# STM32_microcontroller_Power.net
KiCad netlist of a schematic drawn in Altium Designer
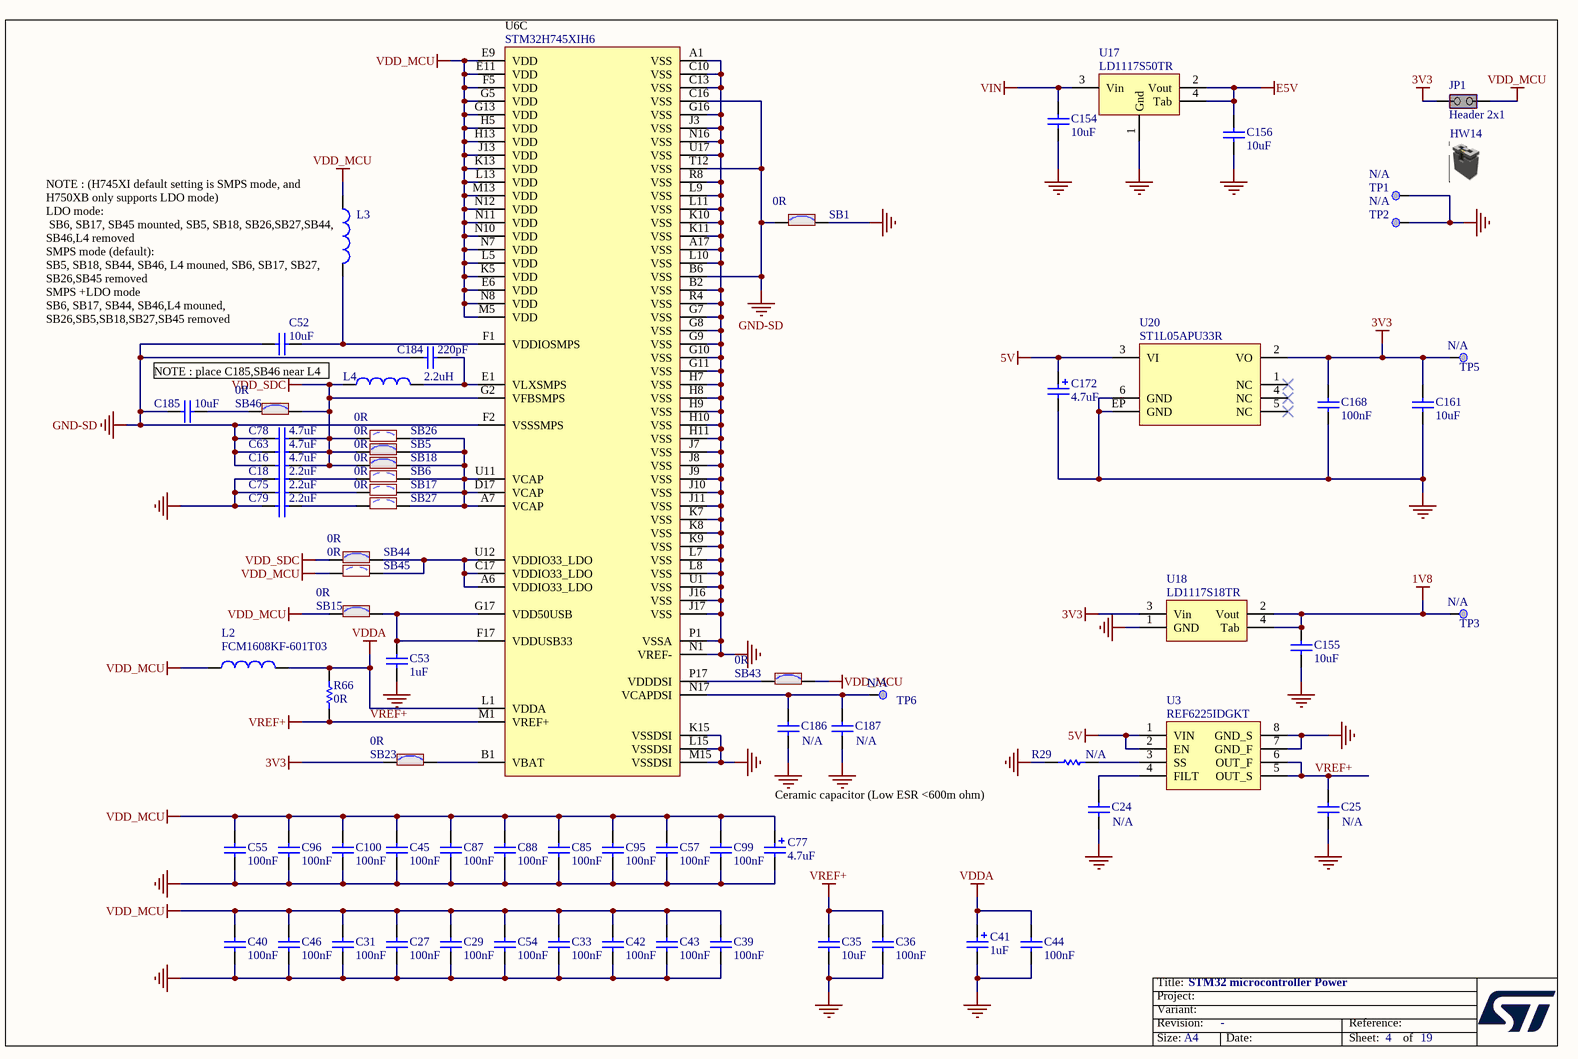
[diagram p0: STM32_microcontroller_Power.SchDoc]

(export (version "E")
  (design (tool "Eeschema 10.0.6"))
  (components
    (comp (ref "C16")
      (value "4.7uF")
      (footprint "C0402")
      (description "Capacitor, MLCC, 4.7uF, 6V3, X5R, 20%, 0402, T=0,5mm")
      (fields
        (field (name "INTERNAL_PART_NUMBER") "MCD-01356")
        (field (name "MANUFACTURER_PART_NUMBER") "GRM155R60J475ME47")
        (field (name "PROVIDED_BY") "Subcon")
      )
      (libsource (lib "MCD_PARTS_database") (part "Capacitor"))
    )
    (comp (ref "C18")
      (value "2.2uF")
      (footprint "C0603")
      (description "Capacitor, MLCC, 2.2uF, 10V, X5R, 10%, 0603, T=0,8mm")
      (fields
        (field (name "INTERNAL_PART_NUMBER") "MCD-00012")
        (field (name "MANUFACTURER_PART_NUMBER") "CC0603KRX5R6BB225")
        (field (name "PROVIDED_BY") "Subcon")
      )
      (libsource (lib "MCD_PARTS_database") (part "Capacitor"))
    )
    (comp (ref "C24")
      (value "N/A")
      (footprint "C0603")
      (description "Capacitor, MLCC, 1uF, 16V, X5R, 10%, 0603, T=0,8mm")
      (fields
        (field (name "INTERNAL_PART_NUMBER") "MCD-00010")
        (field (name "MANUFACTURER_PART_NUMBER") "CC0603KRX5R7BB105")
        (field (name "PROVIDED_BY") "Subcon")
      )
      (libsource (lib "MCD_PARTS_database") (part "Capacitor"))
    )
    (comp (ref "C25")
      (value "N/A")
      (footprint "C1210")
      (description "Capacitor, MLCC, 22uF, 16V, 1210, X7R, 20%, T=2,5mm, ESR 2mohm@410KHz")
      (fields
        (field (name "INTERNAL_PART_NUMBER") "MCD-00614")
        (field (name "MANUFACTURER_PART_NUMBER") "GCM32ER71C226ME19")
        (field (name "PROVIDED_BY") "Subcon")
      )
      (libsource (lib "MCD_PARTS_database") (part "Capacitor"))
    )
    (comp (ref "C27")
      (value "100nF")
      (footprint "C0402")
      (description "Capacitor, MLCC, 100nF, 16V, X7R, +/-10%, 0402, T=0.5mm")
      (fields
        (field (name "INTERNAL_PART_NUMBER") "MCD-00006")
        (field (name "MANUFACTURER_PART_NUMBER") "CC0402KRX7R7BB104")
      )
      (libsource (lib "MCD_PARTS_database") (part "Capacitor"))
    )
    (comp (ref "C29")
      (value "100nF")
      (footprint "C0402")
      (description "Capacitor, MLCC, 100nF, 16V, X7R, +/-10%, 0402, T=0.5mm")
      (fields
        (field (name "INTERNAL_PART_NUMBER") "MCD-00006")
        (field (name "MANUFACTURER_PART_NUMBER") "CC0402KRX7R7BB104")
      )
      (libsource (lib "MCD_PARTS_database") (part "Capacitor"))
    )
    (comp (ref "C31")
      (value "100nF")
      (footprint "C0402")
      (description "Capacitor, MLCC, 100nF, 16V, X7R, +/-10%, 0402, T=0.5mm")
      (fields
        (field (name "INTERNAL_PART_NUMBER") "MCD-00006")
        (field (name "MANUFACTURER_PART_NUMBER") "CC0402KRX7R7BB104")
      )
      (libsource (lib "MCD_PARTS_database") (part "Capacitor"))
    )
    (comp (ref "C33")
      (value "100nF")
      (footprint "C0402")
      (description "Capacitor, MLCC, 100nF, 16V, X7R, +/-10%, 0402, T=0.5mm")
      (fields
        (field (name "INTERNAL_PART_NUMBER") "MCD-00006")
        (field (name "MANUFACTURER_PART_NUMBER") "CC0402KRX7R7BB104")
      )
      (libsource (lib "MCD_PARTS_database") (part "Capacitor"))
    )
    (comp (ref "C35")
      (value "10uF")
      (footprint "C0805")
      (description "Capacitor, MLCC, 10uF, 25V, X5R, 10%, 0805, T=0,85mm")
      (fields
        (field (name "INTERNAL_PART_NUMBER") "MCD-00014")
        (field (name "MANUFACTURER_PART_NUMBER") "CC0805KRX5R8BB106")
        (field (name "PROVIDED_BY") "Subcon")
      )
      (libsource (lib "MCD_PARTS_database") (part "Capacitor"))
    )
    (comp (ref "C36")
      (value "100nF")
      (footprint "C0402")
      (description "Capacitor, MLCC, 100nF, 16V, X7R, +/-10%, 0402, T=0.5mm")
      (fields
        (field (name "INTERNAL_PART_NUMBER") "MCD-00006")
        (field (name "MANUFACTURER_PART_NUMBER") "CC0402KRX7R7BB104")
      )
      (libsource (lib "MCD_PARTS_database") (part "Capacitor"))
    )
    (comp (ref "C39")
      (value "100nF")
      (footprint "C0402")
      (description "Capacitor, MLCC, 100nF, 16V, X7R, +/-10%, 0402, T=0.5mm")
      (fields
        (field (name "INTERNAL_PART_NUMBER") "MCD-00006")
        (field (name "MANUFACTURER_PART_NUMBER") "CC0402KRX7R7BB104")
      )
      (libsource (lib "MCD_PARTS_database") (part "Capacitor"))
    )
    (comp (ref "C40")
      (value "100nF")
      (footprint "C0402")
      (description "Capacitor, MLCC, 100nF, 16V, X7R, +/-10%, 0402, T=0.5mm")
      (fields
        (field (name "INTERNAL_PART_NUMBER") "MCD-00006")
        (field (name "MANUFACTURER_PART_NUMBER") "CC0402KRX7R7BB104")
      )
      (libsource (lib "MCD_PARTS_database") (part "Capacitor"))
    )
    (comp (ref "C41")
      (value "1uF")
      (footprint "CPOL_VISHAY_TANTAL-595D_1407_H220")
      (description "Capacitor, Tantalum, 1uF, 35V, +/-10%, 595D case A")
      (fields
        (field (name "INTERNAL_PART_NUMBER") "MCD-00594")
        (field (name "MANUFACTURER_PART_NUMBER") "595D105X9035A2T")
        (field (name "PROVIDED_BY") "Subcon")
      )
      (libsource (lib "MCD_PARTS_database") (part "Cap_POL_TANA"))
    )
    (comp (ref "C42")
      (value "100nF")
      (footprint "C0402")
      (description "Capacitor, MLCC, 100nF, 16V, X7R, +/-10%, 0402, T=0.5mm")
      (fields
        (field (name "INTERNAL_PART_NUMBER") "MCD-00006")
        (field (name "MANUFACTURER_PART_NUMBER") "CC0402KRX7R7BB104")
      )
      (libsource (lib "MCD_PARTS_database") (part "Capacitor"))
    )
    (comp (ref "C43")
      (value "100nF")
      (footprint "C0402")
      (description "Capacitor, MLCC, 100nF, 16V, X7R, +/-10%, 0402, T=0.5mm")
      (fields
        (field (name "INTERNAL_PART_NUMBER") "MCD-00006")
        (field (name "MANUFACTURER_PART_NUMBER") "CC0402KRX7R7BB104")
      )
      (libsource (lib "MCD_PARTS_database") (part "Capacitor"))
    )
    (comp (ref "C44")
      (value "100nF")
      (footprint "C0402")
      (description "Capacitor, MLCC, 100nF, 16V, X7R, +/-10%, 0402, T=0.5mm")
      (fields
        (field (name "INTERNAL_PART_NUMBER") "MCD-00006")
        (field (name "MANUFACTURER_PART_NUMBER") "CC0402KRX7R7BB104")
      )
      (libsource (lib "MCD_PARTS_database") (part "Capacitor"))
    )
    (comp (ref "C45")
      (value "100nF")
      (footprint "C0402")
      (description "Capacitor, MLCC, 100nF, 16V, X7R, +/-10%, 0402, T=0.5mm")
      (fields
        (field (name "INTERNAL_PART_NUMBER") "MCD-00006")
        (field (name "MANUFACTURER_PART_NUMBER") "CC0402KRX7R7BB104")
      )
      (libsource (lib "MCD_PARTS_database") (part "Capacitor"))
    )
    (comp (ref "C46")
      (value "100nF")
      (footprint "C0402")
      (description "Capacitor, MLCC, 100nF, 16V, X7R, +/-10%, 0402, T=0.5mm")
      (fields
        (field (name "INTERNAL_PART_NUMBER") "MCD-00006")
        (field (name "MANUFACTURER_PART_NUMBER") "CC0402KRX7R7BB104")
      )
      (libsource (lib "MCD_PARTS_database") (part "Capacitor"))
    )
    (comp (ref "C52")
      (value "10uF")
      (footprint "C0402")
      (description "Capacitor, MLCC, 10uF, 4V, X5R, 20%, 0402, T=0,5mm")
      (fields
        (field (name "INTERNAL_PART_NUMBER") "MCD-01355")
        (field (name "MANUFACTURER_PART_NUMBER") "GRM155R60G106ME44")
        (field (name "PROVIDED_BY") "Subcon")
      )
      (libsource (lib "MCD_PARTS_database") (part "Capacitor"))
    )
    (comp (ref "C53")
      (value "1uF")
      (footprint "C0603")
      (description "Capacitor, MLCC, 1uF, 16V, X5R, 10%, 0603, T=0,8mm")
      (fields
        (field (name "INTERNAL_PART_NUMBER") "MCD-00010")
        (field (name "MANUFACTURER_PART_NUMBER") "CC0603KRX5R7BB105")
        (field (name "PROVIDED_BY") "Subcon")
      )
      (libsource (lib "MCD_PARTS_database") (part "Capacitor"))
    )
    (comp (ref "C54")
      (value "100nF")
      (footprint "C0402")
      (description "Capacitor, MLCC, 100nF, 16V, X7R, +/-10%, 0402, T=0.5mm")
      (fields
        (field (name "INTERNAL_PART_NUMBER") "MCD-00006")
        (field (name "MANUFACTURER_PART_NUMBER") "CC0402KRX7R7BB104")
      )
      (libsource (lib "MCD_PARTS_database") (part "Capacitor"))
    )
    (comp (ref "C55")
      (value "100nF")
      (footprint "C0402")
      (description "Capacitor, MLCC, 100nF, 16V, X7R, +/-10%, 0402, T=0.5mm")
      (fields
        (field (name "INTERNAL_PART_NUMBER") "MCD-00006")
        (field (name "MANUFACTURER_PART_NUMBER") "CC0402KRX7R7BB104")
      )
      (libsource (lib "MCD_PARTS_database") (part "Capacitor"))
    )
    (comp (ref "C57")
      (value "100nF")
      (footprint "C0402")
      (description "Capacitor, MLCC, 100nF, 16V, X7R, +/-10%, 0402, T=0.5mm")
      (fields
        (field (name "INTERNAL_PART_NUMBER") "MCD-00006")
        (field (name "MANUFACTURER_PART_NUMBER") "CC0402KRX7R7BB104")
      )
      (libsource (lib "MCD_PARTS_database") (part "Capacitor"))
    )
    (comp (ref "C63")
      (value "4.7uF")
      (footprint "C0402")
      (description "Capacitor, MLCC, 4.7uF, 6V3, X5R, 20%, 0402, T=0,5mm")
      (fields
        (field (name "INTERNAL_PART_NUMBER") "MCD-01356")
        (field (name "MANUFACTURER_PART_NUMBER") "GRM155R60J475ME47")
        (field (name "PROVIDED_BY") "Subcon")
      )
      (libsource (lib "MCD_PARTS_database") (part "Capacitor"))
    )
    (comp (ref "C75")
      (value "2.2uF")
      (footprint "C0603")
      (description "Capacitor, MLCC, 2.2uF, 10V, X5R, 10%, 0603, T=0,8mm")
      (fields
        (field (name "INTERNAL_PART_NUMBER") "MCD-00012")
        (field (name "MANUFACTURER_PART_NUMBER") "CC0603KRX5R6BB225")
        (field (name "PROVIDED_BY") "Subcon")
      )
      (libsource (lib "MCD_PARTS_database") (part "Capacitor"))
    )
    (comp (ref "C77")
      (value "4.7uF")
      (footprint "CPOL_VISHAY_TANTAL-595D_1407_H220")
      (description "Capacitor, Tantalum, 4.7uF, 16V, +/-10%, 595D case A")
      (fields
        (field (name "INTERNAL_PART_NUMBER") "MCD-00595")
        (field (name "MANUFACTURER_PART_NUMBER") "595D475X9016A2T")
        (field (name "PROVIDED_BY") "Subcon")
      )
      (libsource (lib "MCD_PARTS_database") (part "Cap_POL_TANA"))
    )
    (comp (ref "C78")
      (value "4.7uF")
      (footprint "C0402")
      (description "Capacitor, MLCC, 4.7uF, 6V3, X5R, 20%, 0402, T=0,5mm")
      (fields
        (field (name "INTERNAL_PART_NUMBER") "MCD-01356")
        (field (name "MANUFACTURER_PART_NUMBER") "GRM155R60J475ME47")
        (field (name "PROVIDED_BY") "Subcon")
      )
      (libsource (lib "MCD_PARTS_database") (part "Capacitor"))
    )
    (comp (ref "C79")
      (value "2.2uF")
      (footprint "C0603")
      (description "Capacitor, MLCC, 2.2uF, 10V, X5R, 10%, 0603, T=0,8mm")
      (fields
        (field (name "INTERNAL_PART_NUMBER") "MCD-00012")
        (field (name "MANUFACTURER_PART_NUMBER") "CC0603KRX5R6BB225")
        (field (name "PROVIDED_BY") "Subcon")
      )
      (libsource (lib "MCD_PARTS_database") (part "Capacitor"))
    )
    (comp (ref "C85")
      (value "100nF")
      (footprint "C0402")
      (description "Capacitor, MLCC, 100nF, 16V, X7R, +/-10%, 0402, T=0.5mm")
      (fields
        (field (name "INTERNAL_PART_NUMBER") "MCD-00006")
        (field (name "MANUFACTURER_PART_NUMBER") "CC0402KRX7R7BB104")
      )
      (libsource (lib "MCD_PARTS_database") (part "Capacitor"))
    )
    (comp (ref "C87")
      (value "100nF")
      (footprint "C0402")
      (description "Capacitor, MLCC, 100nF, 16V, X7R, +/-10%, 0402, T=0.5mm")
      (fields
        (field (name "INTERNAL_PART_NUMBER") "MCD-00006")
        (field (name "MANUFACTURER_PART_NUMBER") "CC0402KRX7R7BB104")
      )
      (libsource (lib "MCD_PARTS_database") (part "Capacitor"))
    )
    (comp (ref "C88")
      (value "100nF")
      (footprint "C0402")
      (description "Capacitor, MLCC, 100nF, 16V, X7R, +/-10%, 0402, T=0.5mm")
      (fields
        (field (name "INTERNAL_PART_NUMBER") "MCD-00006")
        (field (name "MANUFACTURER_PART_NUMBER") "CC0402KRX7R7BB104")
      )
      (libsource (lib "MCD_PARTS_database") (part "Capacitor"))
    )
    (comp (ref "C95")
      (value "100nF")
      (footprint "C0402")
      (description "Capacitor, MLCC, 100nF, 16V, X7R, +/-10%, 0402, T=0.5mm")
      (fields
        (field (name "INTERNAL_PART_NUMBER") "MCD-00006")
        (field (name "MANUFACTURER_PART_NUMBER") "CC0402KRX7R7BB104")
      )
      (libsource (lib "MCD_PARTS_database") (part "Capacitor"))
    )
    (comp (ref "C96")
      (value "100nF")
      (footprint "C0402")
      (description "Capacitor, MLCC, 100nF, 16V, X7R, +/-10%, 0402, T=0.5mm")
      (fields
        (field (name "INTERNAL_PART_NUMBER") "MCD-00006")
        (field (name "MANUFACTURER_PART_NUMBER") "CC0402KRX7R7BB104")
      )
      (libsource (lib "MCD_PARTS_database") (part "Capacitor"))
    )
    (comp (ref "C99")
      (value "100nF")
      (footprint "C0402")
      (description "Capacitor, MLCC, 100nF, 16V, X7R, +/-10%, 0402, T=0.5mm")
      (fields
        (field (name "INTERNAL_PART_NUMBER") "MCD-00006")
        (field (name "MANUFACTURER_PART_NUMBER") "CC0402KRX7R7BB104")
      )
      (libsource (lib "MCD_PARTS_database") (part "Capacitor"))
    )
    (comp (ref "C100")
      (value "100nF")
      (footprint "C0402")
      (description "Capacitor, MLCC, 100nF, 16V, X7R, +/-10%, 0402, T=0.5mm")
      (fields
        (field (name "INTERNAL_PART_NUMBER") "MCD-00006")
        (field (name "MANUFACTURER_PART_NUMBER") "CC0402KRX7R7BB104")
      )
      (libsource (lib "MCD_PARTS_database") (part "Capacitor"))
    )
    (comp (ref "C154")
      (value "10uF")
      (footprint "C0805")
      (description "Capacitor, MLCC, 10uF, 25V, X5R, 10%, 0805, T=0,85mm")
      (fields
        (field (name "INTERNAL_PART_NUMBER") "MCD-00014")
        (field (name "MANUFACTURER_PART_NUMBER") "CC0805KRX5R8BB106")
        (field (name "PROVIDED_BY") "Subcon")
      )
      (libsource (lib "MCD_PARTS_database") (part "Capacitor"))
    )
    (comp (ref "C155")
      (value "10uF")
      (footprint "C0805")
      (description "Capacitor, MLCC, 10uF, 25V, X5R, 10%, 0805, T=0,85mm")
      (fields
        (field (name "INTERNAL_PART_NUMBER") "MCD-00014")
        (field (name "MANUFACTURER_PART_NUMBER") "CC0805KRX5R8BB106")
        (field (name "PROVIDED_BY") "Subcon")
      )
      (libsource (lib "MCD_PARTS_database") (part "Capacitor"))
    )
    (comp (ref "C156")
      (value "10uF")
      (footprint "C0805")
      (description "Capacitor, MLCC, 10uF, 25V, X5R, 10%, 0805, T=0,85mm")
      (fields
        (field (name "INTERNAL_PART_NUMBER") "MCD-00014")
        (field (name "MANUFACTURER_PART_NUMBER") "CC0805KRX5R8BB106")
        (field (name "PROVIDED_BY") "Subcon")
      )
      (libsource (lib "MCD_PARTS_database") (part "Capacitor"))
    )
    (comp (ref "C161")
      (value "10uF")
      (footprint "C0805")
      (description "Capacitor, MLCC, 10uF, 25V, X5R, 10%, 0805, T=0,85mm")
      (fields
        (field (name "INTERNAL_PART_NUMBER") "MCD-00014")
        (field (name "MANUFACTURER_PART_NUMBER") "CC0805KRX5R8BB106")
        (field (name "PROVIDED_BY") "Subcon")
      )
      (libsource (lib "MCD_PARTS_database") (part "Capacitor"))
    )
    (comp (ref "C168")
      (value "100nF")
      (footprint "C0402")
      (description "Capacitor, MLCC, 100nF, 16V, X7R, +/-10%, 0402, T=0.5mm")
      (fields
        (field (name "INTERNAL_PART_NUMBER") "MCD-00006")
        (field (name "MANUFACTURER_PART_NUMBER") "CC0402KRX7R7BB104")
      )
      (libsource (lib "MCD_PARTS_database") (part "Capacitor"))
    )
    (comp (ref "C172")
      (value "4.7uF")
      (footprint "CPOL_VISHAY_TANTAL-595D_1407_H220")
      (description "Capacitor, Tantalum, 4.7uF, 16V, +/-10%, 595D case A")
      (fields
        (field (name "INTERNAL_PART_NUMBER") "MCD-00595")
        (field (name "MANUFACTURER_PART_NUMBER") "595D475X9016A2T")
        (field (name "PROVIDED_BY") "Subcon")
      )
      (libsource (lib "MCD_PARTS_database") (part "Cap_POL_TANA"))
    )
    (comp (ref "C184")
      (value "220pF")
      (footprint "C0402")
      (description "Capacitor, MLCC, 220pF, 50V, NPO, 5%, 0402, T=0,5mm")
      (fields
        (field (name "INTERNAL_PART_NUMBER") "MCD-01225")
        (field (name "MANUFACTURER_PART_NUMBER") "CC0402JRNPO9BN221")
        (field (name "PROVIDED_BY") "Subcon")
      )
      (libsource (lib "MCD_PARTS_database") (part "Capacitor"))
    )
    (comp (ref "C185")
      (value "10uF")
      (footprint "C0603")
      (description "Capacitor, MLCC, 10uF, 6V3, X5R, 20%, 0603, T=0,8mm")
      (fields
        (field (name "INTERNAL_PART_NUMBER") "MCD-01341")
        (field (name "MANUFACTURER_PART_NUMBER") "GRM188R60J106ME47D")
        (field (name "PROVIDED_BY") "Subcon")
      )
      (libsource (lib "MCD_PARTS_database") (part "Capacitor"))
    )
    (comp (ref "C186")
      (value "N/A")
      (footprint "C0603")
      (description "Capacitor, MLCC, 2.2uF, 10V, X5R, 10%, 0603, T=0,8mm")
      (fields
        (field (name "INTERNAL_PART_NUMBER") "MCD-00012")
        (field (name "MANUFACTURER_PART_NUMBER") "CC0603KRX5R6BB225")
        (field (name "PROVIDED_BY") "Subcon")
      )
      (libsource (lib "MCD_PARTS_database") (part "Capacitor"))
    )
    (comp (ref "C187")
      (value "N/A")
      (footprint "C0402")
      (description "Capacitor, MLCC, 100nF, 16V, X7R, +/-10%, 0402, T=0.5mm")
      (fields
        (field (name "INTERNAL_PART_NUMBER") "MCD-00006")
        (field (name "MANUFACTURER_PART_NUMBER") "CC0402KRX7R7BB104")
      )
      (libsource (lib "MCD_PARTS_database") (part "Capacitor"))
    )
    (comp (ref "HW14")
      (value "Shunt 2.54mm")
      (footprint "N/A")
      (description "SHUNT 2.54mm BLACK")
      (fields
        (field (name "INTERNAL_PART_NUMBER") "MCD-00043")
        (field (name "MANUFACTURER_PART_NUMBER") "SNT-100-BK-G")
        (field (name "PROVIDED_BY") "Subcon")
      )
      (libsource (lib "MCD_PARTS_database") (part "Shunt 2.54mm"))
    )
    (comp (ref "JP1")
      (value "Header 2x1")
      (footprint "CON_SAMTEC_TSW-102-07-G-S")
      (description "Header, 2x1, 2.54mm, VR, TH, T=5.84mm/2.54mm")
      (fields
        (field (name "INTERNAL_PART_NUMBER") "MCD-00683")
        (field (name "MANUFACTURER_PART_NUMBER") "TSW-102-07-G-S")
      )
      (libsource (lib "MCD_PARTS_database") (part "Jumper_Header 2x1 Fitted"))
    )
    (comp (ref "L2")
      (value "BEAD")
      (footprint "L0603")
      (description "Ferrite bead, 600R @1 00MHz, +/-25%, 350mA, 0R5, 0603, T=0.8mm")
      (fields
        (field (name "INTERNAL_PART_NUMBER") "MCD-00047")
        (field (name "MANUFACTURER_PART_NUMBER") "FCM1608KF-601T03")
        (field (name "MANUFACTURER") "TAI-TECH")
      )
      (libsource (lib "MCD_PARTS_database") (part "BEAD"))
    )
    (comp (ref "L3")
      (value "Inductor")
      (footprint "IND_TAIYO-YUDEN_FBMJ1608")
      (description "Ferrite bead, 18R @ 100MHz, +/-30%, 750mA, 0R004, 0603, T=1mm")
      (fields
        (field (name "INTERNAL_PART_NUMBER") "MCD-01431")
        (field (name "MANUFACTURER_PART_NUMBER") "FBMJ1608HM180NTR")
      )
      (libsource (lib "MCD_PARTS_database") (part "Inductor"))
    )
    (comp (ref "L4")
      (value "2.2uH")
      (footprint "IND_2016_MURATA_LQM2MPN2R2NG0")
      (description "Inductor 2.2uH, 2x1.6x0.9mm")
      (fields
        (field (name "INTERNAL_PART_NUMBER") "MCD-01110")
        (field (name "MANUFACTURER_PART_NUMBER") "LQM2MPN2R2NG0")
        (field (name "PROVIDED_BY") "Subcon")
      )
      (libsource (lib "MCD_PARTS_database") (part "Inductor"))
    )
    (comp (ref "R29")
      (value "N/A")
      (footprint "R0402")
      (description "Resistor,120K,0402,1%,1/16W")
      (fields
        (field (name "INTERNAL_PART_NUMBER") "MCD-00166")
        (field (name "MANUFACTURER_PART_NUMBER") "RC0402FR-07120KL")
        (field (name "PROVIDED_BY") "Subcon")
      )
      (libsource (lib "MCD_PARTS_database") (part "Resistor"))
    )
    (comp (ref "R66")
      (value "0R")
      (footprint "R0603")
      (description "Resistor,0R,0603,ULO")
      (fields
        (field (name "INTERNAL_PART_NUMBER") "MCD-00181")
        (field (name "MANUFACTURER_PART_NUMBER") "PMR03EZPJ000")
        (field (name "PROVIDED_BY") "Subcon")
      )
      (libsource (lib "MCD_PARTS_database") (part "Resistor"))
    )
    (comp (ref "SB1")
      (value "0R")
      (footprint "SOLDER-BRIDGE_R0603-0R")
      (description "Solder Bridge ON")
      (fields
        (field (name "INTERNAL_PART_NUMBER") "MCD-00071")
        (field (name "MANUFACTURER") "YAGEO")
        (field (name "PROVIDED_BY") "Subcon")
      )
      (libsource (lib "MCD_PARTS_database") (part "SB_ON"))
    )
    (comp (ref "SB5")
      (value "0R")
      (footprint "SOLDER-BRIDGE_R0603-0R")
      (description "Solder Bridge ON")
      (fields
        (field (name "INTERNAL_PART_NUMBER") "MCD-00071")
        (field (name "MANUFACTURER") "YAGEO")
        (field (name "PROVIDED_BY") "Subcon")
      )
      (libsource (lib "MCD_PARTS_database") (part "SB_ON"))
    )
    (comp (ref "SB6")
      (value "0R")
      (footprint "SOLDER-BRIDGE_R0603-0R")
      (description "Solder Bridge OFF")
      (fields (field (name "INTERNAL_PART_NUMBER") "MCD-00072") (field (name "MANUFACTURER") "YAGEO"))
      (libsource (lib "MCD_PARTS_database") (part "SB_OFF"))
    )
    (comp (ref "SB15")
      (value "0R")
      (footprint "SOLDER-BRIDGE_R0603-0R")
      (description "Solder Bridge ON")
      (fields
        (field (name "INTERNAL_PART_NUMBER") "MCD-00071")
        (field (name "MANUFACTURER") "YAGEO")
        (field (name "PROVIDED_BY") "Subcon")
      )
      (libsource (lib "MCD_PARTS_database") (part "SB_ON"))
    )
    (comp (ref "SB17")
      (value "0R")
      (footprint "SOLDER-BRIDGE_R0603-0R")
      (description "Solder Bridge OFF")
      (fields (field (name "INTERNAL_PART_NUMBER") "MCD-00072") (field (name "MANUFACTURER") "YAGEO"))
      (libsource (lib "MCD_PARTS_database") (part "SB_OFF"))
    )
    (comp (ref "SB18")
      (value "0R")
      (footprint "SOLDER-BRIDGE_R0603-0R")
      (description "Solder Bridge ON")
      (fields
        (field (name "INTERNAL_PART_NUMBER") "MCD-00071")
        (field (name "MANUFACTURER") "YAGEO")
        (field (name "PROVIDED_BY") "Subcon")
      )
      (libsource (lib "MCD_PARTS_database") (part "SB_ON"))
    )
    (comp (ref "SB23")
      (value "0R")
      (footprint "SOLDER-BRIDGE_R0603-0R")
      (description "Solder Bridge ON")
      (fields
        (field (name "INTERNAL_PART_NUMBER") "MCD-00071")
        (field (name "MANUFACTURER") "YAGEO")
        (field (name "PROVIDED_BY") "Subcon")
      )
      (libsource (lib "MCD_PARTS_database") (part "SB_ON"))
    )
    (comp (ref "SB26")
      (value "0R")
      (footprint "SOLDER-BRIDGE_R0603-0R")
      (description "Solder Bridge OFF")
      (fields (field (name "INTERNAL_PART_NUMBER") "MCD-00072") (field (name "MANUFACTURER") "YAGEO"))
      (libsource (lib "MCD_PARTS_database") (part "SB_OFF"))
    )
    (comp (ref "SB27")
      (value "0R")
      (footprint "SOLDER-BRIDGE_R0603-0R")
      (description "Solder Bridge OFF")
      (fields (field (name "INTERNAL_PART_NUMBER") "MCD-00072") (field (name "MANUFACTURER") "YAGEO"))
      (libsource (lib "MCD_PARTS_database") (part "SB_OFF"))
    )
    (comp (ref "SB43")
      (value "0R")
      (footprint "SOLDER-BRIDGE_R0603-0R")
      (description "Solder Bridge ON")
      (fields
        (field (name "INTERNAL_PART_NUMBER") "MCD-00071")
        (field (name "MANUFACTURER") "YAGEO")
        (field (name "PROVIDED_BY") "Subcon")
      )
      (libsource (lib "MCD_PARTS_database") (part "SB_ON"))
    )
    (comp (ref "SB44")
      (value "0R")
      (footprint "SOLDER-BRIDGE_R0603-0R")
      (description "Solder Bridge ON")
      (fields
        (field (name "INTERNAL_PART_NUMBER") "MCD-00071")
        (field (name "MANUFACTURER") "YAGEO")
        (field (name "PROVIDED_BY") "Subcon")
      )
      (libsource (lib "MCD_PARTS_database") (part "SB_ON"))
    )
    (comp (ref "SB45")
      (value "0R")
      (footprint "SOLDER-BRIDGE_R0603-0R")
      (description "Solder Bridge OFF")
      (fields (field (name "INTERNAL_PART_NUMBER") "MCD-00072") (field (name "MANUFACTURER") "YAGEO"))
      (libsource (lib "MCD_PARTS_database") (part "SB_OFF"))
    )
    (comp (ref "SB46")
      (value "0R")
      (footprint "SOLDER-BRIDGE_R0603-0R")
      (description "Solder Bridge ON")
      (fields
        (field (name "INTERNAL_PART_NUMBER") "MCD-00071")
        (field (name "MANUFACTURER") "YAGEO")
        (field (name "PROVIDED_BY") "Subcon")
      )
      (libsource (lib "MCD_PARTS_database") (part "SB_ON"))
    )
    (comp (ref "TP1")
      (value "N/A")
      (footprint "TP_SMD_0-3MM")
      (description "Test Point 0.3mm")
      (fields (field (name "INTERNAL_PART_NUMBER") "MCD-00630") (field (name "Comment") "Test Point"))
      (libsource (lib "") (part "Test Point_1"))
    )
    (comp (ref "TP2")
      (value "N/A")
      (footprint "TP_SMD_0-3MM")
      (description "Test Point 0.3mm")
      (fields (field (name "INTERNAL_PART_NUMBER") "MCD-00630") (field (name "Comment") "Test Point"))
      (libsource (lib "") (part "Test Point_1"))
    )
    (comp (ref "TP3")
      (value "N/A")
      (footprint "TP_SMD_0-3MM")
      (description "Test Point 0.3mm")
      (fields (field (name "INTERNAL_PART_NUMBER") "MCD-00630") (field (name "Comment") "Test Point"))
      (libsource (lib "MCD_PARTS_database") (part "Test Point"))
    )
    (comp (ref "TP5")
      (value "N/A")
      (footprint "TP_SMD_0-3MM")
      (description "Test Point 0.3mm")
      (fields (field (name "INTERNAL_PART_NUMBER") "MCD-00630") (field (name "Comment") "Test Point"))
      (libsource (lib "MCD_PARTS_database") (part "Test Point"))
    )
    (comp (ref "TP6")
      (value "N/A")
      (footprint "TP_SMD_0-3MM")
      (description "Test Point 0.3mm")
      (fields (field (name "INTERNAL_PART_NUMBER") "MCD-00630") (field (name "Comment") "Test Point"))
      (libsource (lib "MCD_PARTS_database") (part "Test Point"))
    )
    (comp (ref "U3")
      (value "REF6225IDGKT")
      (footprint "ICC_VSSOP8_DGK_S-PDSO-G8_3X3_P065")
      (description "IC VREF SERIES 2.5V 8VSSOP")
      (fields
        (field (name "INTERNAL_PART_NUMBER") "MCD-01138")
        (field (name "MANUFACTURER") "TEXAS INSTRUMENTS")
        (field (name "PROVIDED_BY") "Subcon")
      )
      (libsource (lib "MCD_PARTS_database") (part "REF6225IDGKT"))
    )
    (comp (ref "U6")
      (value "STM32H745XIH6")
      (footprint "ICC_TFBGA240+25_14X14_STM32H745H6U_P080")
      (description "32bit MCU TFBGA240+25")
      (fields
        (field (name "INTERNAL_PART_NUMBER") "MCD-01085")
        (field (name "MANUFACTURER") "STMICROELECTRONICS")
        (field (name "PROVIDED_BY") "STM")
      )
      (libsource (lib "MCD_PARTS_database") (part "STM32H745XIH6"))
    )
    (comp (ref "U17")
      (value "LD1117S50TR")
      (footprint "REG_SOT223-TAB")
      (description "IC REG LDO 5V 0.8A SOT223")
      (fields
        (field (name "INTERNAL_PART_NUMBER") "MCD-00088")
        (field (name "MANUFACTURER") "STMICROELECTRONICS")
        (field (name "PROVIDED_BY") "Subcon")
      )
      (libsource (lib "MCD_PARTS_database") (part "LD1117S50TR"))
    )
    (comp (ref "U18")
      (value "LD1117S18TR")
      (footprint "REG_SOT223-TAB")
      (description "Adjustable and fixed low drop positive voltage regulator")
      (fields
        (field (name "INTERNAL_PART_NUMBER") "MCD-01070")
        (field (name "MANUFACTURER") "STMICROELECTRONICS")
        (field (name "PROVIDED_BY") "Subcon")
      )
      (libsource (lib "MCD_PARTS_database") (part "LD1117S18TR"))
    )
    (comp (ref "U20")
      (value "ST1L05APU33R")
      (footprint "ICC_DFN6-EPAD_3X3_P095")
      (description "IC REG LDO 3.3V 1.3A 6DFN")
      (fields
        (field (name "INTERNAL_PART_NUMBER") "MCD-01127")
        (field (name "MANUFACTURER") "STMICROELECTRONICS")
        (field (name "PROVIDED_BY") "Subcon")
      )
      (libsource (lib "MCD_PARTS_database") (part "ST1L05APU33R"))
    )
  )
  (nets
    (net (code "1") (name "1V8") (class "Default")
      (node (ref "C155") (pin "2") (pinfunction "2_2") (pintype "passive"))
      (node (ref "TP3") (pin "1") (pinfunction "1_1") (pintype "passive"))
      (node (ref "U18") (pin "2") (pinfunction "Vout_2") (pintype "power_in"))
      (node (ref "U18") (pin "4") (pinfunction "Tab_4") (pintype "power_in"))
    )
    (net (code "2") (name "3V3") (class "Default")
      (node (ref "C161") (pin "2") (pinfunction "2_2") (pintype "passive"))
      (node (ref "C168") (pin "1") (pinfunction "1_1") (pintype "passive"))
      (node (ref "JP1") (pin "2") (pinfunction "NO_2") (pintype "passive"))
      (node (ref "SB23") (pin "1") (pinfunction "1_1") (pintype "passive"))
      (node (ref "TP5") (pin "1") (pinfunction "1_1") (pintype "passive"))
      (node (ref "U18") (pin "3") (pinfunction "Vin_3") (pintype "power_in"))
      (node (ref "U20") (pin "2") (pinfunction "VO_2") (pintype "passive"))
    )
    (net (code "3") (name "5V") (class "Default")
      (node (ref "C172") (pin "1") (pinfunction "1_1") (pintype "passive"))
      (node (ref "U20") (pin "3") (pinfunction "VI_3") (pintype "passive"))
      (node (ref "U3") (pin "1") (pinfunction "VIN_1") (pintype "passive"))
      (node (ref "U3") (pin "2") (pinfunction "EN_2") (pintype "passive"))
    )
    (net (code "4") (name "E5V") (class "Default")
      (node (ref "C156") (pin "2") (pinfunction "2_2") (pintype "passive"))
      (node (ref "U17") (pin "2") (pinfunction "Vout_2") (pintype "passive"))
      (node (ref "U17") (pin "4") (pinfunction "Tab_4") (pintype "passive"))
    )
    (net (code "5") (name "GND") (class "Default")
      (node (ref "C100") (pin "1") (pinfunction "1_1") (pintype "passive"))
      (node (ref "C154") (pin "1") (pinfunction "1_1") (pintype "passive"))
      (node (ref "C155") (pin "1") (pinfunction "1_1") (pintype "passive"))
      (node (ref "C156") (pin "1") (pinfunction "1_1") (pintype "passive"))
      (node (ref "C161") (pin "1") (pinfunction "1_1") (pintype "passive"))
      (node (ref "C168") (pin "2") (pinfunction "2_2") (pintype "passive"))
      (node (ref "C172") (pin "2") (pinfunction "2_2") (pintype "passive"))
      (node (ref "C18") (pin "1") (pinfunction "1_1") (pintype "passive"))
      (node (ref "C186") (pin "1") (pinfunction "1_1") (pintype "passive"))
      (node (ref "C187") (pin "1") (pinfunction "1_1") (pintype "passive"))
      (node (ref "C24") (pin "1") (pinfunction "1_1") (pintype "passive"))
      (node (ref "C25") (pin "1") (pinfunction "1_1") (pintype "passive"))
      (node (ref "C27") (pin "1") (pinfunction "1_1") (pintype "passive"))
      (node (ref "C29") (pin "1") (pinfunction "1_1") (pintype "passive"))
      (node (ref "C31") (pin "1") (pinfunction "1_1") (pintype "passive"))
      (node (ref "C33") (pin "1") (pinfunction "1_1") (pintype "passive"))
      (node (ref "C35") (pin "1") (pinfunction "1_1") (pintype "passive"))
      (node (ref "C36") (pin "1") (pinfunction "1_1") (pintype "passive"))
      (node (ref "C39") (pin "1") (pinfunction "1_1") (pintype "passive"))
      (node (ref "C40") (pin "1") (pinfunction "1_1") (pintype "passive"))
      (node (ref "C41") (pin "2") (pinfunction "2_2") (pintype "passive"))
      (node (ref "C42") (pin "1") (pinfunction "1_1") (pintype "passive"))
      (node (ref "C43") (pin "1") (pinfunction "1_1") (pintype "passive"))
      (node (ref "C44") (pin "1") (pinfunction "1_1") (pintype "passive"))
      (node (ref "C45") (pin "1") (pinfunction "1_1") (pintype "passive"))
      (node (ref "C46") (pin "1") (pinfunction "1_1") (pintype "passive"))
      (node (ref "C53") (pin "1") (pinfunction "1_1") (pintype "passive"))
      (node (ref "C54") (pin "1") (pinfunction "1_1") (pintype "passive"))
      (node (ref "C55") (pin "1") (pinfunction "1_1") (pintype "passive"))
      (node (ref "C57") (pin "1") (pinfunction "1_1") (pintype "passive"))
      (node (ref "C75") (pin "1") (pinfunction "1_1") (pintype "passive"))
      (node (ref "C77") (pin "2") (pinfunction "2_2") (pintype "passive"))
      (node (ref "C79") (pin "1") (pinfunction "1_1") (pintype "passive"))
      (node (ref "C85") (pin "1") (pinfunction "1_1") (pintype "passive"))
      (node (ref "C87") (pin "1") (pinfunction "1_1") (pintype "passive"))
      (node (ref "C88") (pin "1") (pinfunction "1_1") (pintype "passive"))
      (node (ref "C95") (pin "1") (pinfunction "1_1") (pintype "passive"))
      (node (ref "C96") (pin "1") (pinfunction "1_1") (pintype "passive"))
      (node (ref "C99") (pin "1") (pinfunction "1_1") (pintype "passive"))
      (node (ref "R29") (pin "1") (pinfunction "1_1") (pintype "passive"))
      (node (ref "SB1") (pin "2") (pinfunction "2_2") (pintype "passive"))
      (node (ref "TP1") (pin "1") (pinfunction "1_1") (pintype "passive"))
      (node (ref "TP2") (pin "1") (pinfunction "1_1") (pintype "passive"))
      (node (ref "U17") (pin "1") (pinfunction "Gnd_1") (pintype "passive"))
      (node (ref "U18") (pin "1") (pinfunction "GND_1") (pintype "power_in"))
      (node (ref "U20") (pin "6") (pinfunction "GND_6") (pintype "passive"))
      (node (ref "U20") (pin "EP") (pinfunction "GND_EP") (pintype "passive"))
      (node (ref "U3") (pin "7") (pinfunction "GND_F_7") (pintype "passive"))
      (node (ref "U3") (pin "8") (pinfunction "GND_S_8") (pintype "passive"))
      (node (ref "U6") (pin "A1") (pinfunction "VSS_A1") (pintype "passive"))
      (node (ref "U6") (pin "A17") (pinfunction "VSS_A17") (pintype "passive"))
      (node (ref "U6") (pin "B2") (pinfunction "VSS_B2") (pintype "passive"))
      (node (ref "U6") (pin "C10") (pinfunction "VSS_C10") (pintype "passive"))
      (node (ref "U6") (pin "C13") (pinfunction "VSS_C13") (pintype "passive"))
      (node (ref "U6") (pin "G10") (pinfunction "VSS_G10") (pintype "passive"))
      (node (ref "U6") (pin "G11") (pinfunction "VSS_G11") (pintype "passive"))
      (node (ref "U6") (pin "G16") (pinfunction "VSS_G16") (pintype "passive"))
      (node (ref "U6") (pin "G7") (pinfunction "VSS_G7") (pintype "passive"))
      (node (ref "U6") (pin "G8") (pinfunction "VSS_G8") (pintype "passive"))
      (node (ref "U6") (pin "G9") (pinfunction "VSS_G9") (pintype "passive"))
      (node (ref "U6") (pin "H10") (pinfunction "VSS_H10") (pintype "passive"))
      (node (ref "U6") (pin "H11") (pinfunction "VSS_H11") (pintype "passive"))
      (node (ref "U6") (pin "H7") (pinfunction "VSS_H7") (pintype "passive"))
      (node (ref "U6") (pin "H8") (pinfunction "VSS_H8") (pintype "passive"))
      (node (ref "U6") (pin "H9") (pinfunction "VSS_H9") (pintype "passive"))
      (node (ref "U6") (pin "J10") (pinfunction "VSS_J10") (pintype "passive"))
      (node (ref "U6") (pin "J11") (pinfunction "VSS_J11") (pintype "passive"))
      (node (ref "U6") (pin "J16") (pinfunction "VSS_J16") (pintype "passive"))
      (node (ref "U6") (pin "J17") (pinfunction "VSS_J17") (pintype "passive"))
      (node (ref "U6") (pin "J3") (pinfunction "VSS_J3") (pintype "passive"))
      (node (ref "U6") (pin "J7") (pinfunction "VSS_J7") (pintype "passive"))
      (node (ref "U6") (pin "J8") (pinfunction "VSS_J8") (pintype "passive"))
      (node (ref "U6") (pin "J9") (pinfunction "VSS_J9") (pintype "passive"))
      (node (ref "U6") (pin "K10") (pinfunction "VSS_K10") (pintype "passive"))
      (node (ref "U6") (pin "K11") (pinfunction "VSS_K11") (pintype "passive"))
      (node (ref "U6") (pin "K15") (pinfunction "VSSDSI_K15") (pintype "passive"))
      (node (ref "U6") (pin "K7") (pinfunction "VSS_K7") (pintype "passive"))
      (node (ref "U6") (pin "K8") (pinfunction "VSS_K8") (pintype "passive"))
      (node (ref "U6") (pin "K9") (pinfunction "VSS_K9") (pintype "passive"))
      (node (ref "U6") (pin "L10") (pinfunction "VSS_L10") (pintype "passive"))
      (node (ref "U6") (pin "L11") (pinfunction "VSS_L11") (pintype "passive"))
      (node (ref "U6") (pin "L15") (pinfunction "VSSDSI_L15") (pintype "passive"))
      (node (ref "U6") (pin "L7") (pinfunction "VSS_L7") (pintype "passive"))
      (node (ref "U6") (pin "L8") (pinfunction "VSS_L8") (pintype "passive"))
      (node (ref "U6") (pin "L9") (pinfunction "VSS_L9") (pintype "passive"))
      (node (ref "U6") (pin "M15") (pinfunction "VSSDSI_M15") (pintype "passive"))
      (node (ref "U6") (pin "N1") (pinfunction "VREF-_N1") (pintype "passive"))
      (node (ref "U6") (pin "N16") (pinfunction "VSS_N16") (pintype "passive"))
      (node (ref "U6") (pin "P1") (pinfunction "VSSA_P1") (pintype "passive"))
      (node (ref "U6") (pin "R4") (pinfunction "VSS_R4") (pintype "passive"))
      (node (ref "U6") (pin "R8") (pinfunction "VSS_R8") (pintype "passive"))
      (node (ref "U6") (pin "U1") (pinfunction "VSS_U1") (pintype "passive"))
      (node (ref "U6") (pin "U17") (pinfunction "VSS_U17") (pintype "passive"))
    )
    (net (code "6") (name "GND-SD") (class "Default")
      (node (ref "C16") (pin "2") (pinfunction "2_2") (pintype "passive"))
      (node (ref "C184") (pin "1") (pinfunction "1_1") (pintype "passive"))
      (node (ref "C185") (pin "1") (pinfunction "1_1") (pintype "passive"))
      (node (ref "C52") (pin "1") (pinfunction "1_1") (pintype "passive"))
      (node (ref "C63") (pin "2") (pinfunction "2_2") (pintype "passive"))
      (node (ref "C78") (pin "2") (pinfunction "2_2") (pintype "passive"))
      (node (ref "SB1") (pin "1") (pinfunction "1_1") (pintype "passive"))
      (node (ref "U6") (pin "B6") (pinfunction "VSS_B6") (pintype "passive"))
      (node (ref "U6") (pin "C16") (pinfunction "VSS_C16") (pintype "passive"))
      (node (ref "U6") (pin "F2") (pinfunction "VSSSMPS_F2") (pintype "passive"))
      (node (ref "U6") (pin "T12") (pinfunction "VSS_T12") (pintype "passive"))
    )
    (net (code "7") (name "Net-(C18-Pad2)") (class "Default")
      (node (ref "C18") (pin "2") (pinfunction "2_2") (pintype "passive"))
      (node (ref "SB6") (pin "1") (pinfunction "1_1") (pintype "passive"))
    )
    (net (code "8") (name "Net-(C75-Pad2)") (class "Default")
      (node (ref "C75") (pin "2") (pinfunction "2_2") (pintype "passive"))
      (node (ref "SB17") (pin "1") (pinfunction "1_1") (pintype "passive"))
    )
    (net (code "9") (name "Net-(C79-Pad2)") (class "Default")
      (node (ref "C79") (pin "2") (pinfunction "2_2") (pintype "passive"))
      (node (ref "SB27") (pin "1") (pinfunction "1_1") (pintype "passive"))
    )
    (net (code "10") (name "Net-(C185-Pad2)") (class "Default")
      (node (ref "C185") (pin "2") (pinfunction "2_2") (pintype "passive"))
      (node (ref "SB46") (pin "1") (pinfunction "1_1") (pintype "passive"))
    )
    (net (code "11") (name "Net-(SB17-Pad2)") (class "Default")
      (node (ref "SB17") (pin "2") (pinfunction "2_2") (pintype "passive"))
      (node (ref "SB18") (pin "2") (pinfunction "2_2") (pintype "passive"))
      (node (ref "SB26") (pin "2") (pinfunction "2_2") (pintype "passive"))
      (node (ref "SB27") (pin "2") (pinfunction "2_2") (pintype "passive"))
      (node (ref "SB5") (pin "2") (pinfunction "2_2") (pintype "passive"))
      (node (ref "SB6") (pin "2") (pinfunction "2_2") (pintype "passive"))
      (node (ref "U6") (pin "A7") (pinfunction "VCAP_A7") (pintype "passive"))
      (node (ref "U6") (pin "D17") (pinfunction "VCAP_D17") (pintype "passive"))
      (node (ref "U6") (pin "U11") (pinfunction "VCAP_U11") (pintype "passive"))
    )
    (net (code "12") (name "Net-(SB44-Pad2)") (class "Default")
      (node (ref "SB44") (pin "2") (pinfunction "2_2") (pintype "passive"))
      (node (ref "SB45") (pin "2") (pinfunction "2_2") (pintype "passive"))
      (node (ref "U6") (pin "A6") (pinfunction "VDDIO33_LDO_A6") (pintype "passive"))
      (node (ref "U6") (pin "C17") (pinfunction "VDDIO33_LDO_C17") (pintype "passive"))
      (node (ref "U6") (pin "U12") (pinfunction "VDDIO33_LDO_U12") (pintype "passive"))
    )
    (net (code "13") (name "Net-(U3-FILT)") (class "Default")
      (node (ref "C24") (pin "2") (pinfunction "2_2") (pintype "passive"))
      (node (ref "U3") (pin "4") (pinfunction "FILT_4") (pintype "passive"))
    )
    (net (code "14") (name "Net-(U3-SS)") (class "Default")
      (node (ref "R29") (pin "2") (pinfunction "2_2") (pintype "passive"))
      (node (ref "U3") (pin "3") (pinfunction "SS_3") (pintype "passive"))
    )
    (net (code "15") (name "Net-(U6C-VBAT)") (class "Default")
      (node (ref "SB23") (pin "2") (pinfunction "2_2") (pintype "passive"))
      (node (ref "U6") (pin "B1") (pinfunction "VBAT_B1") (pintype "passive"))
    )
    (net (code "16") (name "Net-(U6C-VCAPDSI)") (class "Default")
      (node (ref "C186") (pin "2") (pinfunction "2_2") (pintype "passive"))
      (node (ref "C187") (pin "2") (pinfunction "2_2") (pintype "passive"))
      (node (ref "TP6") (pin "1") (pinfunction "1_1") (pintype "passive"))
      (node (ref "U6") (pin "N17") (pinfunction "VCAPDSI_N17") (pintype "passive"))
    )
    (net (code "17") (name "Net-(U6C-VDD50USB)") (class "Default")
      (node (ref "C53") (pin "2") (pinfunction "2_2") (pintype "passive"))
      (node (ref "SB15") (pin "2") (pinfunction "2_2") (pintype "passive"))
      (node (ref "U6") (pin "F17") (pinfunction "VDDUSB33_F17") (pintype "passive"))
      (node (ref "U6") (pin "G17") (pinfunction "VDD50USB_G17") (pintype "passive"))
    )
    (net (code "18") (name "Net-(U6C-VDDDSI)") (class "Default")
      (node (ref "SB43") (pin "1") (pinfunction "1_1") (pintype "passive"))
      (node (ref "U6") (pin "P17") (pinfunction "VDDDSI_P17") (pintype "passive"))
    )
    (net (code "19") (name "Net-(U6C-VDDIOSMPS)") (class "Default")
      (node (ref "C52") (pin "2") (pinfunction "2_2") (pintype "passive"))
      (node (ref "L3") (pin "2") (pinfunction "2_2") (pintype "passive"))
      (node (ref "U6") (pin "F1") (pinfunction "VDDIOSMPS_F1") (pintype "passive"))
    )
    (net (code "20") (name "Net-(U6C-VLXSMPS)") (class "Default")
      (node (ref "C184") (pin "2") (pinfunction "2_2") (pintype "passive"))
      (node (ref "L4") (pin "2") (pinfunction "2_2") (pintype "passive"))
      (node (ref "U6") (pin "E1") (pinfunction "VLXSMPS_E1") (pintype "passive"))
    )
    (net (code "21") (name "VDDA") (class "Default")
      (node (ref "C41") (pin "1") (pinfunction "1_1") (pintype "passive"))
      (node (ref "C44") (pin "2") (pinfunction "2_2") (pintype "passive"))
      (node (ref "L2") (pin "2") (pinfunction "2_2") (pintype "passive"))
      (node (ref "R66") (pin "1") (pinfunction "1_1") (pintype "passive"))
      (node (ref "U6") (pin "L1") (pinfunction "VDDA_L1") (pintype "passive"))
    )
    (net (code "22") (name "VDD_MCU") (class "Default")
      (node (ref "C100") (pin "2") (pinfunction "2_2") (pintype "passive"))
      (node (ref "C27") (pin "2") (pinfunction "2_2") (pintype "passive"))
      (node (ref "C29") (pin "2") (pinfunction "2_2") (pintype "passive"))
      (node (ref "C31") (pin "2") (pinfunction "2_2") (pintype "passive"))
      (node (ref "C33") (pin "2") (pinfunction "2_2") (pintype "passive"))
      (node (ref "C39") (pin "2") (pinfunction "2_2") (pintype "passive"))
      (node (ref "C40") (pin "2") (pinfunction "2_2") (pintype "passive"))
      (node (ref "C42") (pin "2") (pinfunction "2_2") (pintype "passive"))
      (node (ref "C43") (pin "2") (pinfunction "2_2") (pintype "passive"))
      (node (ref "C45") (pin "2") (pinfunction "2_2") (pintype "passive"))
      (node (ref "C46") (pin "2") (pinfunction "2_2") (pintype "passive"))
      (node (ref "C54") (pin "2") (pinfunction "2_2") (pintype "passive"))
      (node (ref "C55") (pin "2") (pinfunction "2_2") (pintype "passive"))
      (node (ref "C57") (pin "2") (pinfunction "2_2") (pintype "passive"))
      (node (ref "C77") (pin "1") (pinfunction "1_1") (pintype "passive"))
      (node (ref "C85") (pin "2") (pinfunction "2_2") (pintype "passive"))
      (node (ref "C87") (pin "2") (pinfunction "2_2") (pintype "passive"))
      (node (ref "C88") (pin "2") (pinfunction "2_2") (pintype "passive"))
      (node (ref "C95") (pin "2") (pinfunction "2_2") (pintype "passive"))
      (node (ref "C96") (pin "2") (pinfunction "2_2") (pintype "passive"))
      (node (ref "C99") (pin "2") (pinfunction "2_2") (pintype "passive"))
      (node (ref "JP1") (pin "1") (pinfunction "COMMON_1") (pintype "passive"))
      (node (ref "L2") (pin "1") (pinfunction "1_1") (pintype "passive"))
      (node (ref "L3") (pin "1") (pinfunction "1_1") (pintype "passive"))
      (node (ref "SB15") (pin "1") (pinfunction "1_1") (pintype "passive"))
      (node (ref "SB43") (pin "2") (pinfunction "2_2") (pintype "passive"))
      (node (ref "SB45") (pin "1") (pinfunction "1_1") (pintype "passive"))
      (node (ref "U6") (pin "E11") (pinfunction "VDD_E11") (pintype "passive"))
      (node (ref "U6") (pin "E6") (pinfunction "VDD_E6") (pintype "passive"))
      (node (ref "U6") (pin "E9") (pinfunction "VDD_E9") (pintype "passive"))
      (node (ref "U6") (pin "F5") (pinfunction "VDD_F5") (pintype "passive"))
      (node (ref "U6") (pin "G13") (pinfunction "VDD_G13") (pintype "passive"))
      (node (ref "U6") (pin "G5") (pinfunction "VDD_G5") (pintype "passive"))
      (node (ref "U6") (pin "H13") (pinfunction "VDD_H13") (pintype "passive"))
      (node (ref "U6") (pin "H5") (pinfunction "VDD_H5") (pintype "passive"))
      (node (ref "U6") (pin "J13") (pinfunction "VDD_J13") (pintype "passive"))
      (node (ref "U6") (pin "K13") (pinfunction "VDD_K13") (pintype "passive"))
      (node (ref "U6") (pin "K5") (pinfunction "VDD_K5") (pintype "passive"))
      (node (ref "U6") (pin "L13") (pinfunction "VDD_L13") (pintype "passive"))
      (node (ref "U6") (pin "L5") (pinfunction "VDD_L5") (pintype "passive"))
      (node (ref "U6") (pin "M13") (pinfunction "VDD_M13") (pintype "passive"))
      (node (ref "U6") (pin "M5") (pinfunction "VDD_M5") (pintype "passive"))
      (node (ref "U6") (pin "N10") (pinfunction "VDD_N10") (pintype "passive"))
      (node (ref "U6") (pin "N11") (pinfunction "VDD_N11") (pintype "passive"))
      (node (ref "U6") (pin "N12") (pinfunction "VDD_N12") (pintype "passive"))
      (node (ref "U6") (pin "N7") (pinfunction "VDD_N7") (pintype "passive"))
      (node (ref "U6") (pin "N8") (pinfunction "VDD_N8") (pintype "passive"))
    )
    (net (code "23") (name "VDD_SDC") (class "Default")
      (node (ref "C16") (pin "1") (pinfunction "1_1") (pintype "passive"))
      (node (ref "C63") (pin "1") (pinfunction "1_1") (pintype "passive"))
      (node (ref "C78") (pin "1") (pinfunction "1_1") (pintype "passive"))
      (node (ref "L4") (pin "1") (pinfunction "1_1") (pintype "passive"))
      (node (ref "SB18") (pin "1") (pinfunction "1_1") (pintype "passive"))
      (node (ref "SB26") (pin "1") (pinfunction "1_1") (pintype "passive"))
      (node (ref "SB44") (pin "1") (pinfunction "1_1") (pintype "passive"))
      (node (ref "SB46") (pin "2") (pinfunction "2_2") (pintype "passive"))
      (node (ref "SB5") (pin "1") (pinfunction "1_1") (pintype "passive"))
      (node (ref "U6") (pin "G2") (pinfunction "VFBSMPS_G2") (pintype "passive"))
    )
    (net (code "24") (name "VIN") (class "Default")
      (node (ref "C154") (pin "2") (pinfunction "2_2") (pintype "passive"))
      (node (ref "U17") (pin "3") (pinfunction "Vin_3") (pintype "passive"))
    )
    (net (code "25") (name "VREF+") (class "Default")
      (node (ref "C25") (pin "2") (pinfunction "2_2") (pintype "passive"))
      (node (ref "C35") (pin "2") (pinfunction "2_2") (pintype "passive"))
      (node (ref "C36") (pin "2") (pinfunction "2_2") (pintype "passive"))
      (node (ref "R66") (pin "2") (pinfunction "2_2") (pintype "passive"))
      (node (ref "U3") (pin "5") (pinfunction "OUT_S_5") (pintype "passive"))
      (node (ref "U3") (pin "6") (pinfunction "OUT_F_6") (pintype "passive"))
      (node (ref "U6") (pin "M1") (pinfunction "VREF+_M1") (pintype "passive"))
    )
    (net (code "26") (name "unconnected-(U20-NC-Pad1)") (class "Default")
      (node (ref "U20") (pin "1") (pinfunction "NC_1") (pintype "passive+no_connect"))
    )
    (net (code "27") (name "unconnected-(U20-NC-Pad4)") (class "Default")
      (node (ref "U20") (pin "4") (pinfunction "NC_4") (pintype "passive+no_connect"))
    )
    (net (code "28") (name "unconnected-(U20-NC-Pad5)") (class "Default")
      (node (ref "U20") (pin "5") (pinfunction "NC_5") (pintype "passive+no_connect"))
    )
  )
)
